# Sheet1.net
KiCad netlist of a schematic drawn in Altium Designer
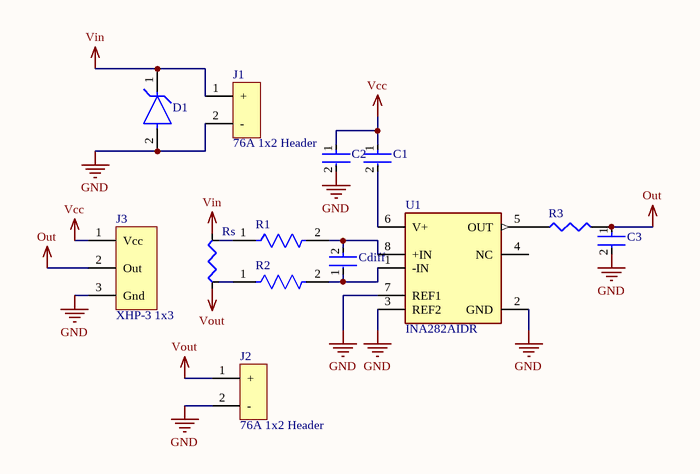
[diagram p0: Sheet1.SchDoc]

(export (version "E")
  (design (tool "Eeschema 10.0.6"))
  (components
    (comp (ref "C1")
      (value "0603B104K500CT")
      (footprint "FP-0603B104K500CT-IPC_C")
      (description "CAP CER 0.1UF 50V X7R 0603")
      (fields (field (name "TOLERANCE") "10%"))
      (libsource (lib "Altium Content Vault") (part "02cd4be3c70576c341d710602a673aa"))
    )
    (comp (ref "C2")
      (value "CL21B105KBFNFNE")
      (footprint "FP-CL21-IPC_C")
      (description "CL21 Series 0805 1uF 50V ±10% Tolerance X7R Multilayer Ceramic Chip Capacitor")
      (fields (field (name "TOLERANCE") "10%"))
      (libsource (lib "Altium Content Vault") (part "b4654b650e69147ec39a6b967a45e02"))
    )
    (comp (ref "C3")
      (value "C0805C103J5RAC7210")
      (footprint "FP-C0805C-DN-MFG")
      (description "CAP CER SMD 0805 .01UF X7R 5% 50")
      (fields
        (field (name "MANUFACTURER") "KEMET")
        (field (name "OCTOPART") "https://octopart.com/c0805c103j5rac7210-kemet-3921106")
      )
      (libsource (lib "Altium Content Vault") (part "b4654b650e69147ec39a6b967a45e02"))
    )
    (comp (ref "Cdiff")
      (value "C1608C0G1H103J080AA")
      (footprint "FP-C1608-080-0_1-IPC_C")
      (description "Multilayer Ceramic Capacitors 10nF ±5% 50V C0G SMD 0603")
      (fields (field (name "TOLERANCE") "5%") (field (name "VOLTAGE") "50V"))
      (libsource (lib "Altium Content Vault") (part "236180d848d6139a670b325ea6854c9"))
    )
    (comp (ref "D1")
      (value "SMAJ33A")
      (footprint "FP-SMAJ-MFG")
      (description "TVS DIODE 33V 53.3V DO214AC")
      (fields
        (field (name "MANUFACTURER") "Littelfuse Inc")
        (field (name "OCTOPART") "https://octopart.com/smaj33a-littelfuse-350074")
      )
      (libsource (lib "Altium Content Vault") (part "f813f71cba58e380607f5dd3caf9714"))
    )
    (comp (ref "J1")
      (value "76A 1x2 Header")
      (description "Conn PC Board Terminal Block 2 POS 10.16mm RA Through Hole 76A Cardboard")
      (fields
        (field (name "MANUFACTURER") "Phoenix Contact")
        (field (name "MANUFACTURER PART NUMBER") "1773976")
      )
      (libsource (lib "Schlib1") (part "1773976"))
    )
    (comp (ref "J2")
      (value "76A 1x2 Header")
      (description "Conn PC Board Terminal Block 2 POS 10.16mm RA Through Hole 76A Cardboard")
      (fields
        (field (name "MANUFACTURER") "Phoenix Contact")
        (field (name "MANUFACTURER PART NUMBER") "1773976")
      )
      (libsource (lib "Schlib1") (part "1773976"))
    )
    (comp (ref "J3")
      (value "XHP-3 1x3")
      (description "Connector Housing, XH Series, 3 Positions, 2.50mm, 250V, 30-22 AWG, Crimp, In-Line, Natural")
      (fields (field (name "MANUFACTURER") "JST") (field (name "MANUFACTURER PART NUMBER") "XHP-3"))
      (libsource (lib "Schlib1") (part "XHP-3"))
    )
    (comp (ref "R1")
      (value "TNPW060310R0BEEA")
      (footprint "FP-TNPW0603-e3-IPC_B")
      (description "RES 10 OHM 0.1% 1/10W 0603")
      (fields (field (name "TOLERANCE") "0.1%"))
      (libsource (lib "Altium Content Vault") (part "1029c3af85768c4190bb7ad29bc67b5"))
    )
    (comp (ref "R2")
      (value "TNPW060310R0BEEA")
      (footprint "FP-TNPW0603-e3-IPC_B")
      (description "RES 10 OHM 0.1% 1/10W 0603")
      (fields (field (name "TOLERANCE") "0.1%"))
      (libsource (lib "Altium Content Vault") (part "1029c3af85768c4190bb7ad29bc67b5"))
    )
    (comp (ref "R3")
      (value "TNPW060310R0FEEA")
      (description "Fixed Resistor, Thin Film, 0.1W, 10ohm, 75V, 1% +/-Tol, 25ppm/Cel, Surface Mount, 0603")
      (fields (field (name "MANUFACTURER") "Vishay") (field (name "TOLERANCE") "1%"))
      (libsource (lib "Schlib1") (part "TNPW060310R0FEEA"))
    )
    (comp (ref "Rs")
      (value "LRMAP3920C-R001FT")
      (description "Fixed Resistor, Metal Strip, 5W, 0.001ohm, 1% +/-Tol, 50ppm/Cel, Surface Mount, 3920")
      (fields (field (name "MANUFACTURER") "Welwyn") (field (name "TOLERANCE") "1%"))
      (libsource (lib "Schlib1") (part "LRMAP3920C-R001FT (2)"))
    )
    (comp (ref "U1")
      (value "INA282AIDR")
      (footprint "FP-D0008A-MFG")
      (description "IC CURRENT SHUNT MONITOR 8SOIC")
      (fields
        (field (name "OCTOPART") "https://octopart.com/ina282aidr-texas+instruments-18804707")
        (field (name "MANUFACTURER") "Texas Instruments")
      )
      (libsource (lib "Altium Content Vault") (part "cde3a58535430d96cf366b62b9f6f9d"))
    )
  )
  (nets
    (net (code "1") (name "GND") (class "Default")
      (node (ref "C2") (pin "2") (pinfunction "2_2") (pintype "passive"))
      (node (ref "C3") (pin "2") (pinfunction "2_2") (pintype "passive"))
      (node (ref "D1") (pin "2") (pinfunction "A_2") (pintype "passive"))
      (node (ref "J1") (pin "2") (pinfunction "-_2") (pintype "passive"))
      (node (ref "J2") (pin "2") (pinfunction "-_2") (pintype "passive"))
      (node (ref "J3") (pin "3") (pinfunction "Gnd_3") (pintype "passive"))
      (node (ref "U1") (pin "2") (pinfunction "GND_2") (pintype "power_in"))
      (node (ref "U1") (pin "3") (pinfunction "REF2_3") (pintype "power_in"))
      (node (ref "U1") (pin "7") (pinfunction "REF1_7") (pintype "power_in"))
    )
    (net (code "2") (name "Net-(Rs-S+)") (class "Default")
      (node (ref "R1") (pin "1") (pinfunction "1_1") (pintype "passive"))
      (node (ref "Rs") (pin "3") (pinfunction "S+_3") (pintype "passive"))
    )
    (net (code "3") (name "Net-(Rs-S-)") (class "Default")
      (node (ref "R2") (pin "1") (pinfunction "1_1") (pintype "passive"))
      (node (ref "Rs") (pin "4") (pinfunction "S-_4") (pintype "passive"))
    )
    (net (code "4") (name "Net-(U1-+IN)") (class "Default")
      (node (ref "Cdiff") (pin "2") (pinfunction "2_2") (pintype "passive"))
      (node (ref "R1") (pin "2") (pinfunction "2_2") (pintype "passive"))
      (node (ref "U1") (pin "8") (pinfunction "+IN_8") (pintype "tri_state"))
    )
    (net (code "5") (name "Net-(U1--IN)") (class "Default")
      (node (ref "Cdiff") (pin "1") (pinfunction "1_1") (pintype "passive"))
      (node (ref "R2") (pin "2") (pinfunction "2_2") (pintype "passive"))
      (node (ref "U1") (pin "1") (pinfunction "-IN_1") (pintype "tri_state"))
    )
    (net (code "6") (name "Net-(U1-OUT)") (class "Default")
      (node (ref "R3") (pin "1") (pinfunction "1_1") (pintype "passive"))
      (node (ref "U1") (pin "5") (pinfunction "OUT_5") (pintype "output"))
    )
    (net (code "7") (name "Net-(U1-V+)") (class "Default")
      (node (ref "C1") (pin "2") (pinfunction "2_2") (pintype "passive"))
      (node (ref "U1") (pin "6") (pinfunction "V+_6") (pintype "power_in"))
    )
    (net (code "8") (name "Out") (class "Default")
      (node (ref "C3") (pin "1") (pinfunction "1_1") (pintype "passive"))
      (node (ref "J3") (pin "2") (pinfunction "Out_2") (pintype "passive"))
      (node (ref "R3") (pin "2") (pinfunction "2_2") (pintype "passive"))
    )
    (net (code "9") (name "Vcc") (class "Default")
      (node (ref "C1") (pin "1") (pinfunction "1_1") (pintype "passive"))
      (node (ref "C2") (pin "1") (pinfunction "1_1") (pintype "passive"))
      (node (ref "J3") (pin "1") (pinfunction "Vcc_1") (pintype "passive"))
    )
    (net (code "10") (name "Vin") (class "Default")
      (node (ref "D1") (pin "1") (pinfunction "C_1") (pintype "passive"))
      (node (ref "J1") (pin "1") (pinfunction "+_1") (pintype "passive"))
      (node (ref "Rs") (pin "2") (pinfunction "2_2") (pintype "passive"))
    )
    (net (code "11") (name "Vout") (class "Default")
      (node (ref "J2") (pin "1") (pinfunction "+_1") (pintype "passive"))
      (node (ref "Rs") (pin "1") (pinfunction "1_1") (pintype "passive"))
    )
    (net (code "12") (name "unconnected-(U1-NC-Pad4)") (class "Default")
      (node (ref "U1") (pin "4") (pinfunction "NC_4") (pintype "passive"))
    )
  )
)
